# EDU_High-Speed-Design_CPU_SD-Card.net
KiCad netlist of a schematic drawn in Altium Designer
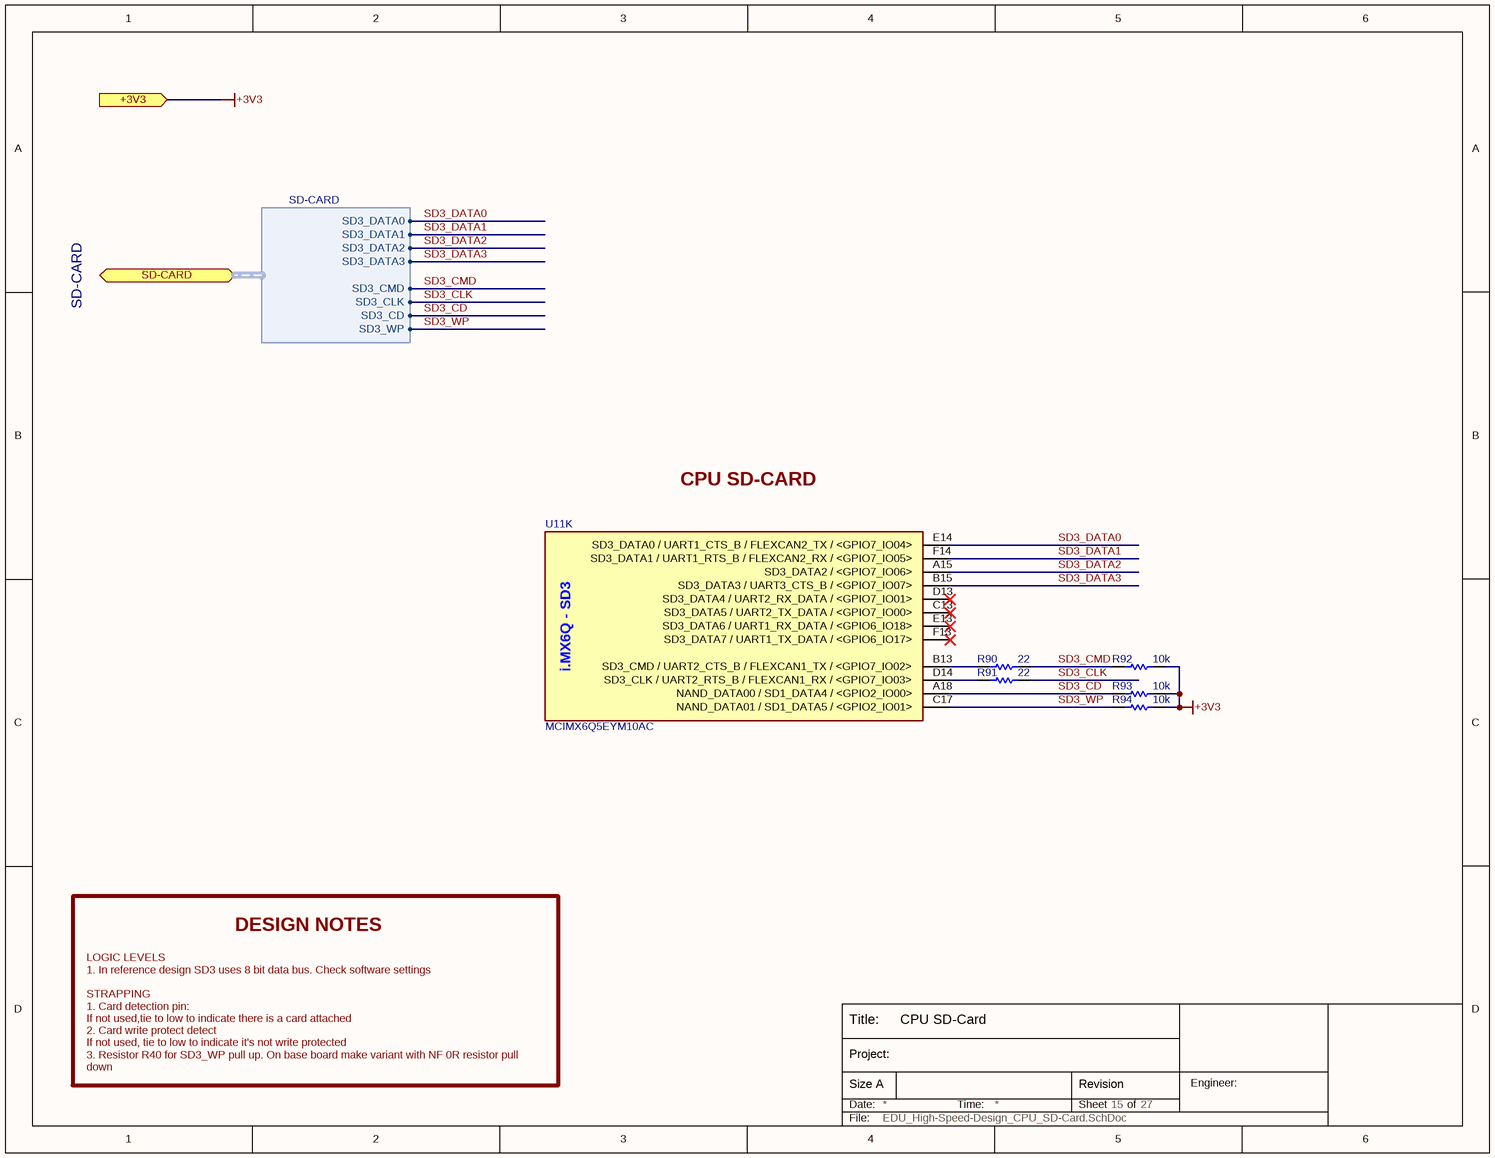
[diagram p0: EDU_High-Speed-Design_CPU_SD-Card.SchDoc]

(export (version "E")
  (design (tool "Eeschema 10.0.6"))
  (components
    (comp (ref "R90")
      (value "22")
      (footprint "R0402")
      (description "RES 22.0 OHM 1/16W 1% 0402 SMD")
      (libsource (lib "EDU_High-Speed-Design") (part "RC0402FR-0722RL"))
    )
    (comp (ref "R91")
      (value "22")
      (footprint "R0402")
      (description "RES 22.0 OHM 1/16W 1% 0402 SMD")
      (libsource (lib "EDU_High-Speed-Design") (part "RC0402FR-0722RL"))
    )
    (comp (ref "R92")
      (value "10k")
      (footprint "R0402")
      (description "RES 10.0K OHM 1/16W 1% 0402 SMD")
      (libsource (lib "EDU_High-Speed-Design") (part "RC0402FR-0710KL"))
    )
    (comp (ref "R93")
      (value "10k")
      (footprint "R0402")
      (description "RES 10.0K OHM 1/16W 1% 0402 SMD")
      (libsource (lib "EDU_High-Speed-Design") (part "RC0402FR-0710KL"))
    )
    (comp (ref "R94")
      (value "10k")
      (footprint "R0402")
      (description "RES 10.0K OHM 1/16W 1% 0402 SMD")
      (libsource (lib "EDU_High-Speed-Design") (part "RC0402FR-0710KL"))
    )
    (comp (ref "U11")
      (value "MCIMX6Q5EYM10AC")
      (footprint "MCIMX6Q5EYM10AC")
      (description "IC MCU 32BIT ARM QUAD 624FCBGA")
      (libsource (lib "EDU_High-Speed-Design") (part "MCIMX6Q5EYM10AC"))
    )
  )
  (nets
    (net (code "2") (name "+3V3") (class "Default")
      (node (ref "R92") (pin "2") (pinfunction "2_2") (pintype "passive"))
      (node (ref "R93") (pin "2") (pinfunction "2_2") (pintype "passive"))
      (node (ref "R94") (pin "2") (pinfunction "2_2") (pintype "passive"))
    )
    (net (code "3") (name "/SD3_CD") (class "Default")
      (node (ref "R93") (pin "1") (pinfunction "1_1") (pintype "passive"))
      (node (ref "U11") (pin "A18") (pinfunction "NAND_DATA00_/_SD1_DATA4_/_<GPIO2_IO00>_A18") (pintype "passive"))
    )
    (net (code "4") (name "/SD3_CLK") (class "Default")
      (node (ref "R91") (pin "1") (pinfunction "1_1") (pintype "passive"))
    )
    (net (code "5") (name "/SD3_CMD") (class "Default")
      (node (ref "R90") (pin "1") (pinfunction "1_1") (pintype "passive"))
      (node (ref "R92") (pin "1") (pinfunction "1_1") (pintype "passive"))
    )
    (net (code "6") (name "/SD3_DATA0") (class "Default")
      (node (ref "U11") (pin "E14") (pinfunction "SD3_DATA0_/_UART1_CTS_B_/_FLEXCAN2_TX_/_<GPIO7_IO04>_E14") (pintype "passive"))
    )
    (net (code "7") (name "/SD3_DATA1") (class "Default")
      (node (ref "U11") (pin "F14") (pinfunction "SD3_DATA1_/_UART1_RTS_B_/_FLEXCAN2_RX_/_<GPIO7_IO05>_F14") (pintype "passive"))
    )
    (net (code "8") (name "/SD3_DATA2") (class "Default")
      (node (ref "U11") (pin "A15") (pinfunction "SD3_DATA2_/_<GPIO7_IO06>_A15") (pintype "passive"))
    )
    (net (code "9") (name "/SD3_DATA3") (class "Default")
      (node (ref "U11") (pin "B15") (pinfunction "SD3_DATA3_/_UART3_CTS_B_/_<GPIO7_IO07>_B15") (pintype "passive"))
    )
    (net (code "10") (name "/SD3_WP") (class "Default")
      (node (ref "R94") (pin "1") (pinfunction "1_1") (pintype "passive"))
      (node (ref "U11") (pin "C17") (pinfunction "NAND_DATA01_/_SD1_DATA5_/_<GPIO2_IO01>_C17") (pintype "passive"))
    )
    (net (code "12") (name "Net-(U11K-SD3_CLK_{slash}_UART2_RTS_B_{slash}_FLEXCAN1_RX_{slash}_<GPIO7_IO03>)") (class "Default")
      (node (ref "R91") (pin "2") (pinfunction "2_2") (pintype "passive"))
      (node (ref "U11") (pin "D14") (pinfunction "SD3_CLK_/_UART2_RTS_B_/_FLEXCAN1_RX_/_<GPIO7_IO03>_D14") (pintype "passive"))
    )
    (net (code "13") (name "Net-(U11K-SD3_CMD_{slash}_UART2_CTS_B_{slash}_FLEXCAN1_TX_{slash}_<GPIO7_IO02>)") (class "Default")
      (node (ref "R90") (pin "2") (pinfunction "2_2") (pintype "passive"))
      (node (ref "U11") (pin "B13") (pinfunction "SD3_CMD_/_UART2_CTS_B_/_FLEXCAN1_TX_/_<GPIO7_IO02>_B13") (pintype "passive"))
    )
    (net (code "14") (name "unconnected-(U11K-SD3_DATA4_{slash}_UART2_RX_DATA_{slash}_<GPIO7_IO01>-PadD13)") (class "Default")
      (node (ref "U11") (pin "D13") (pinfunction "SD3_DATA4_/_UART2_RX_DATA_/_<GPIO7_IO01>_D13") (pintype "passive+no_connect"))
    )
    (net (code "15") (name "unconnected-(U11K-SD3_DATA5_{slash}_UART2_TX_DATA_{slash}_<GPIO7_IO00>-PadC13)") (class "Default")
      (node (ref "U11") (pin "C13") (pinfunction "SD3_DATA5_/_UART2_TX_DATA_/_<GPIO7_IO00>_C13") (pintype "passive+no_connect"))
    )
    (net (code "16") (name "unconnected-(U11K-SD3_DATA6_{slash}_UART1_RX_DATA_{slash}_<GPIO6_IO18>-PadE13)") (class "Default")
      (node (ref "U11") (pin "E13") (pinfunction "SD3_DATA6_/_UART1_RX_DATA_/_<GPIO6_IO18>_E13") (pintype "passive+no_connect"))
    )
    (net (code "17") (name "unconnected-(U11K-SD3_DATA7_{slash}_UART1_TX_DATA_{slash}_<GPIO6_IO17>-PadF13)") (class "Default")
      (node (ref "U11") (pin "F13") (pinfunction "SD3_DATA7_/_UART1_TX_DATA_/_<GPIO6_IO17>_F13") (pintype "passive+no_connect"))
    )
  )
)
